# STM32WL_Sensors.net
KiCad netlist of a schematic drawn in Altium Designer
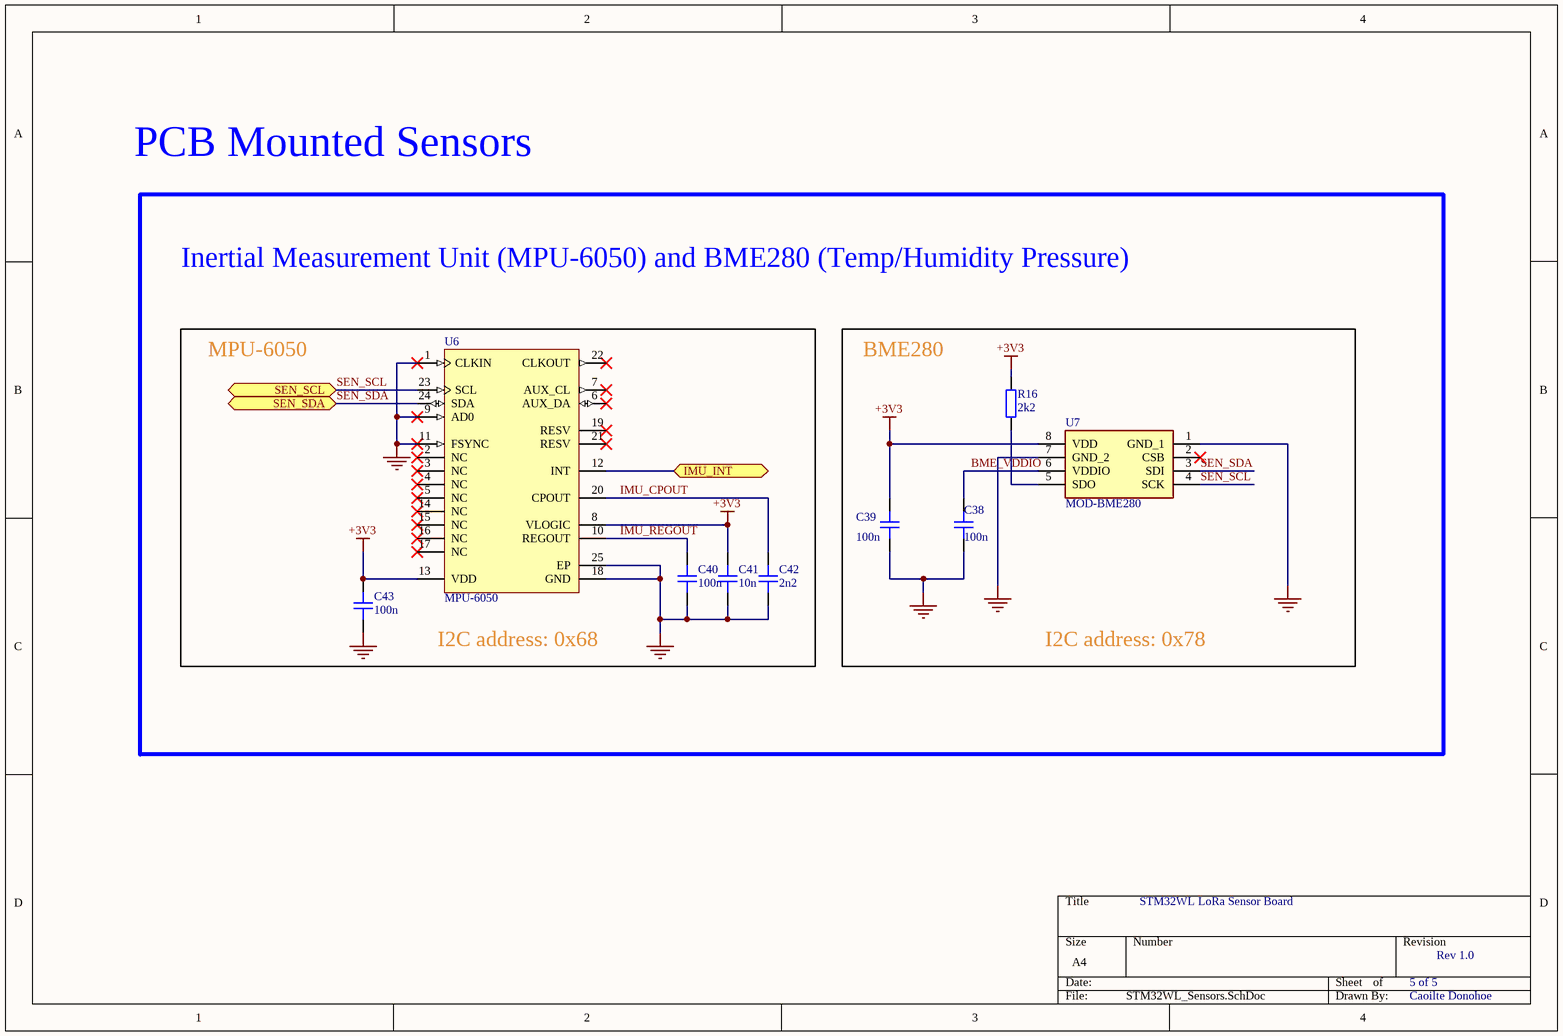
[diagram p0: STM32WL_Sensors.SchDoc]

(export (version "E")
  (design (tool "Eeschema 10.0.6"))
  (components
    (comp (ref "C38")
      (value "100n")
      (footprint "CAP_0402")
      (description "Capacitor SMD 0402 16V")
      (libsource (lib "Schematic-Lib-PhilsLab") (part "CAP_0402_16V"))
    )
    (comp (ref "C39")
      (value "100n")
      (footprint "CAP_0402")
      (description "Capacitor SMD 0402 16V")
      (libsource (lib "Schematic-Lib-PhilsLab") (part "CAP_0402_16V"))
    )
    (comp (ref "C40")
      (value "100n")
      (footprint "CAP_0402")
      (description "Capacitor SMD 0402 16V")
      (libsource (lib "Schematic-Lib-PhilsLab") (part "CAP_0402_16V"))
    )
    (comp (ref "C41")
      (value "10n")
      (footprint "CAP_0402")
      (description "Capacitor SMD 0402 16V")
      (libsource (lib "Schematic-Lib-PhilsLab") (part "CAP_0402_16V"))
    )
    (comp (ref "C42")
      (value "2n2")
      (footprint "CAP_0402")
      (description "Capacitor SMD 0402 16V")
      (libsource (lib "Schematic-Lib-PhilsLab") (part "CAP_0402_16V"))
    )
    (comp (ref "C43")
      (value "100n")
      (footprint "CAP_0402")
      (description "Capacitor SMD 0402 16V")
      (libsource (lib "Schematic-Lib-PhilsLab") (part "CAP_0402_16V"))
    )
    (comp (ref "R16")
      (value "2k2")
      (footprint "RES_0402")
      (description "Resistor SMD 0402")
      (libsource (lib "Schematic-Lib-PhilsLab") (part "RES_0402"))
    )
    (comp (ref "U6")
      (value "MPU-6050")
      (footprint "IS-QFN-24_V")
      (fields (field (name "MANUFACTURER") "InvenSense"))
      (libsource (lib "Altium Content Vault") (part "IS-MPU-6050-QFN-24"))
    )
    (comp (ref "U7")
      (value "MOD-BME280")
      (footprint "SamacSys:MODBME280")
      (description "Integrated Circuit")
      (fields (field (name "MOUSER PART NUMBER") "909-MOD-BME280"))
      (libsource (lib "*") (part "MOD-BME280"))
    )
  )
  (nets
    (net (code "1") (name "+3V3") (class "Default")
      (node (ref "C39") (pin "2") (pinfunction "2_2") (pintype "passive"))
      (node (ref "C41") (pin "2") (pinfunction "2_2") (pintype "passive"))
      (node (ref "C43") (pin "2") (pinfunction "2_2") (pintype "passive"))
      (node (ref "R16") (pin "2") (pinfunction "2_2") (pintype "passive"))
      (node (ref "U6") (pin "13") (pinfunction "VDD_13") (pintype "power_in"))
      (node (ref "U6") (pin "8") (pinfunction "VLOGIC_8") (pintype "power_in"))
      (node (ref "U7") (pin "8") (pinfunction "VDD_8") (pintype "passive"))
    )
    (net (code "3") (name "/BME_VDDIO") (class "Default")
      (node (ref "C38") (pin "2") (pinfunction "2_2") (pintype "passive"))
      (node (ref "U7") (pin "6") (pinfunction "VDDIO_6") (pintype "passive"))
    )
    (net (code "4") (name "/IMU_CPOUT") (class "Default")
      (node (ref "C42") (pin "2") (pinfunction "2_2") (pintype "passive"))
      (node (ref "U6") (pin "20") (pinfunction "CPOUT_20") (pintype "passive"))
    )
    (net (code "5") (name "/IMU_INT") (class "Default")
      (node (ref "U6") (pin "12") (pinfunction "INT_12") (pintype "open_collector"))
    )
    (net (code "6") (name "/IMU_REGOUT") (class "Default")
      (node (ref "C40") (pin "2") (pinfunction "2_2") (pintype "passive"))
      (node (ref "U6") (pin "10") (pinfunction "REGOUT_10") (pintype "passive"))
    )
    (net (code "7") (name "/SEN_SCL") (class "Default")
      (node (ref "U6") (pin "23") (pinfunction "SCL_23") (pintype "input"))
      (node (ref "U7") (pin "4") (pinfunction "SCK_4") (pintype "passive"))
    )
    (net (code "8") (name "/SEN_SDA") (class "Default")
      (node (ref "U6") (pin "24") (pinfunction "SDA_24") (pintype "bidirectional"))
      (node (ref "U7") (pin "3") (pinfunction "SDI_3") (pintype "passive"))
    )
    (net (code "9") (name "GND") (class "Default")
      (node (ref "C38") (pin "1") (pinfunction "1_1") (pintype "passive"))
      (node (ref "C39") (pin "1") (pinfunction "1_1") (pintype "passive"))
      (node (ref "C40") (pin "1") (pinfunction "1_1") (pintype "passive"))
      (node (ref "C41") (pin "1") (pinfunction "1_1") (pintype "passive"))
      (node (ref "C42") (pin "1") (pinfunction "1_1") (pintype "passive"))
      (node (ref "C43") (pin "1") (pinfunction "1_1") (pintype "passive"))
      (node (ref "U6") (pin "1") (pinfunction "CLKIN_1") (pintype "input"))
      (node (ref "U6") (pin "11") (pinfunction "FSYNC_11") (pintype "input"))
      (node (ref "U6") (pin "18") (pinfunction "GND_18") (pintype "power_in"))
      (node (ref "U6") (pin "25") (pinfunction "EP_25") (pintype "power_in"))
      (node (ref "U6") (pin "9") (pinfunction "AD0_9") (pintype "input"))
      (node (ref "U7") (pin "1") (pinfunction "GND_1_1") (pintype "passive"))
      (node (ref "U7") (pin "7") (pinfunction "GND_2_7") (pintype "passive"))
    )
    (net (code "10") (name "Net-(U7-SDO)") (class "Default")
      (node (ref "R16") (pin "1") (pinfunction "1_1") (pintype "passive"))
      (node (ref "U7") (pin "5") (pinfunction "SDO_5") (pintype "passive"))
    )
    (net (code "11") (name "unconnected-(U6-AUX_CL-Pad7)") (class "Default")
      (node (ref "U6") (pin "7") (pinfunction "AUX_CL_7") (pintype "output+no_connect"))
    )
    (net (code "12") (name "unconnected-(U6-AUX_DA-Pad6)") (class "Default")
      (node (ref "U6") (pin "6") (pinfunction "AUX_DA_6") (pintype "bidirectional+no_connect"))
    )
    (net (code "13") (name "unconnected-(U6-CLKOUT-Pad22)") (class "Default")
      (node (ref "U6") (pin "22") (pinfunction "CLKOUT_22") (pintype "output+no_connect"))
    )
    (net (code "14") (name "unconnected-(U6-NC-Pad2)") (class "Default")
      (node (ref "U6") (pin "2") (pinfunction "NC_2") (pintype "passive+no_connect"))
    )
    (net (code "15") (name "unconnected-(U6-NC-Pad3)") (class "Default")
      (node (ref "U6") (pin "3") (pinfunction "NC_3") (pintype "passive+no_connect"))
    )
    (net (code "16") (name "unconnected-(U6-NC-Pad4)") (class "Default")
      (node (ref "U6") (pin "4") (pinfunction "NC_4") (pintype "passive+no_connect"))
    )
    (net (code "17") (name "unconnected-(U6-NC-Pad5)") (class "Default")
      (node (ref "U6") (pin "5") (pinfunction "NC_5") (pintype "passive+no_connect"))
    )
    (net (code "18") (name "unconnected-(U6-NC-Pad14)") (class "Default")
      (node (ref "U6") (pin "14") (pinfunction "NC_14") (pintype "passive+no_connect"))
    )
    (net (code "19") (name "unconnected-(U6-NC-Pad15)") (class "Default")
      (node (ref "U6") (pin "15") (pinfunction "NC_15") (pintype "passive+no_connect"))
    )
    (net (code "20") (name "unconnected-(U6-NC-Pad16)") (class "Default")
      (node (ref "U6") (pin "16") (pinfunction "NC_16") (pintype "passive+no_connect"))
    )
    (net (code "21") (name "unconnected-(U6-NC-Pad17)") (class "Default")
      (node (ref "U6") (pin "17") (pinfunction "NC_17") (pintype "passive+no_connect"))
    )
    (net (code "22") (name "unconnected-(U6-RESV-Pad19)") (class "Default")
      (node (ref "U6") (pin "19") (pinfunction "RESV_19") (pintype "passive+no_connect"))
    )
    (net (code "23") (name "unconnected-(U6-RESV-Pad21)") (class "Default")
      (node (ref "U6") (pin "21") (pinfunction "RESV_21") (pintype "passive+no_connect"))
    )
    (net (code "24") (name "unconnected-(U7-CSB-Pad2)") (class "Default")
      (node (ref "U7") (pin "2") (pinfunction "CSB_2") (pintype "passive+no_connect"))
    )
  )
)
